# 10LA_org_Raspiado_Updated_Logo_Oct3.net
KiCad netlist of a schematic drawn in EAGLE
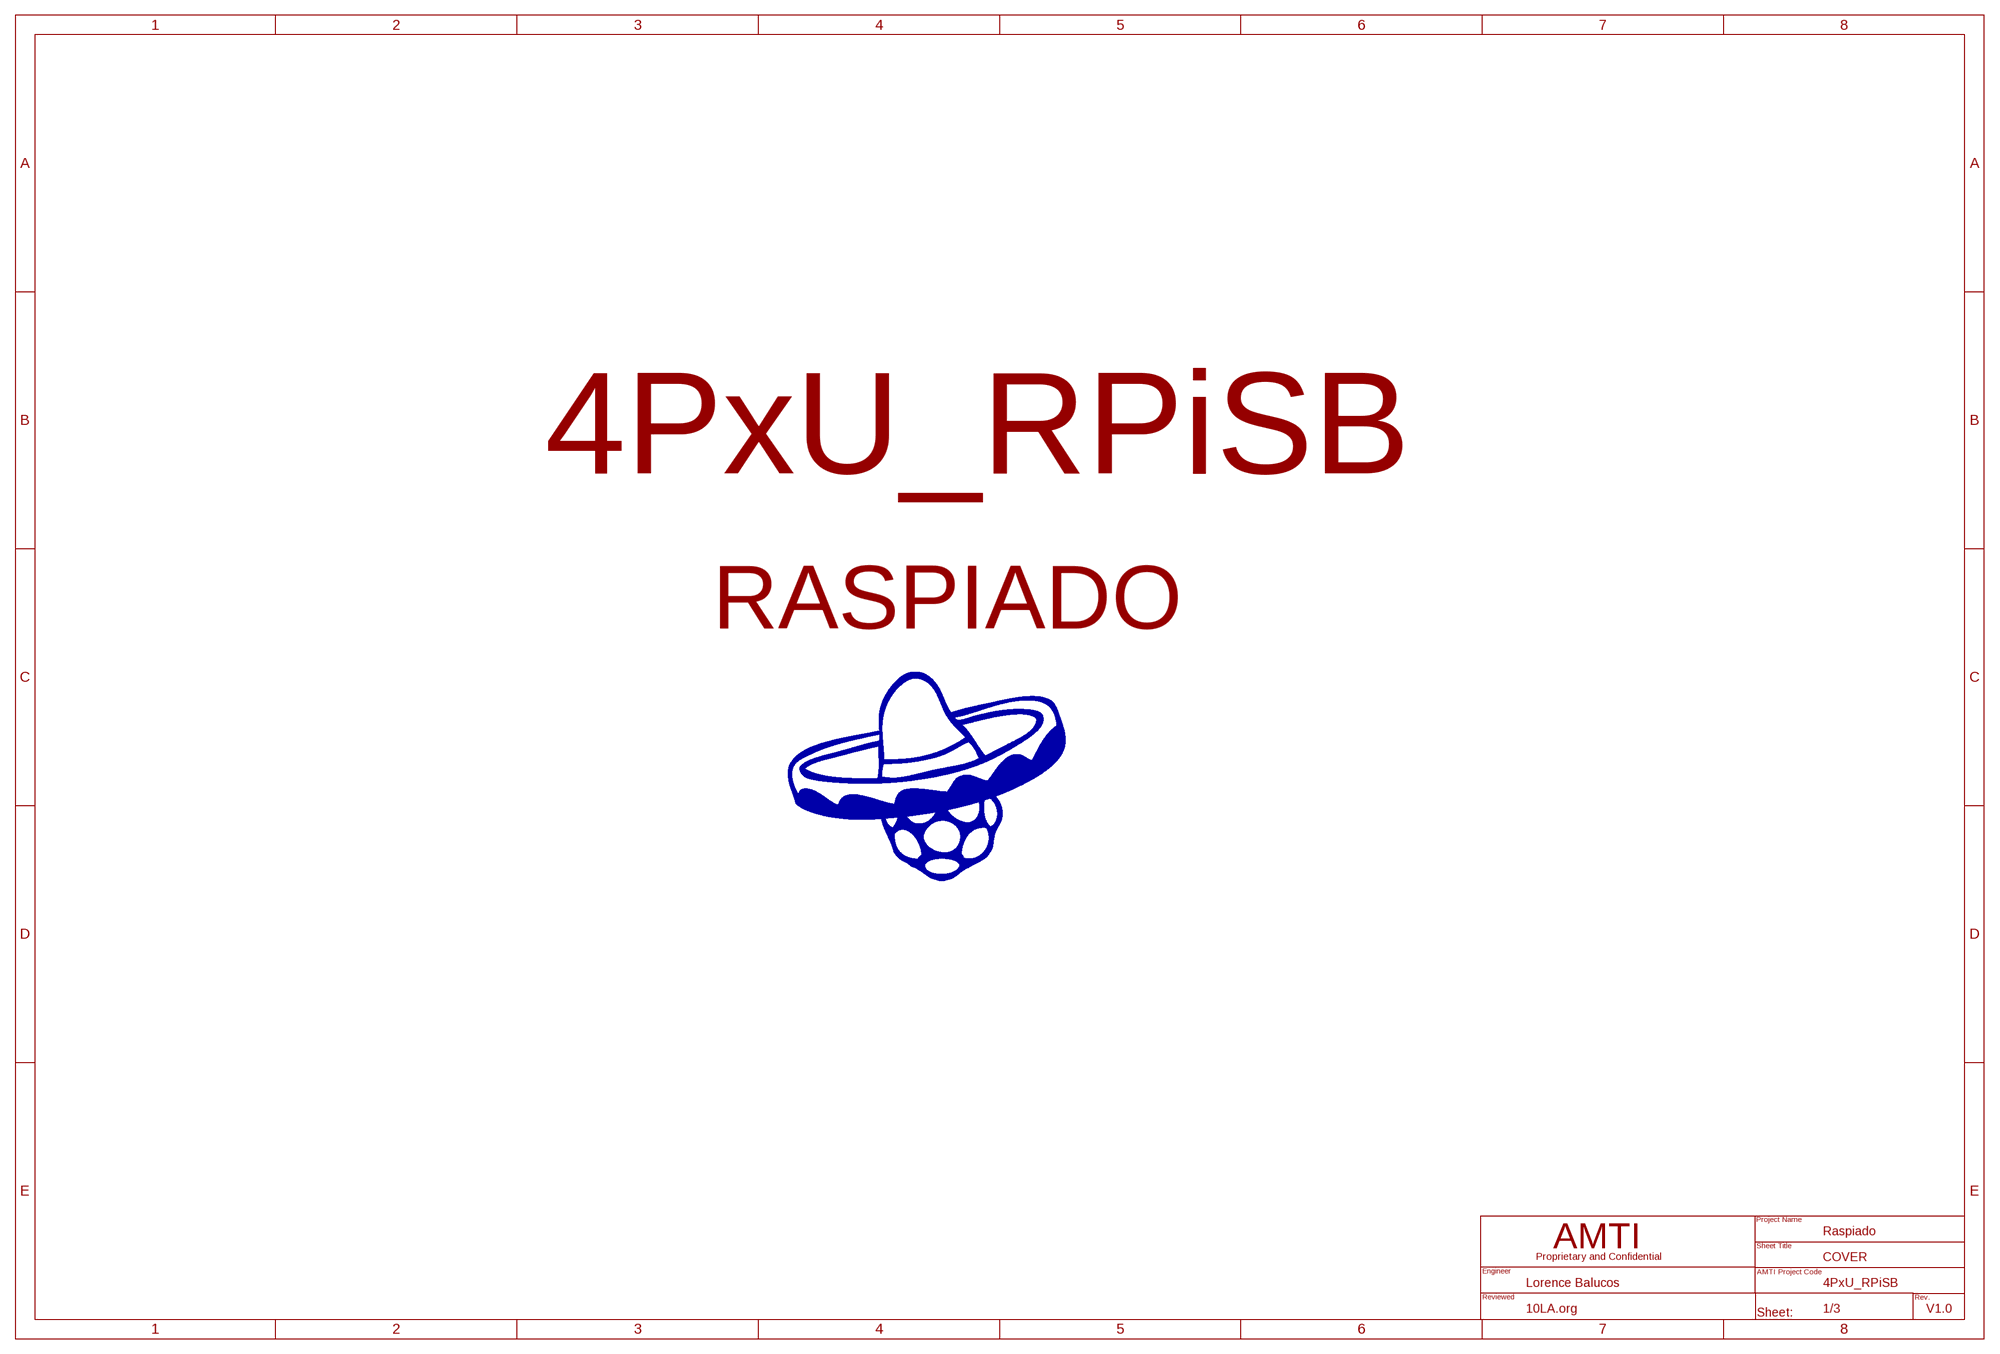
[diagram p0: schematic, sheet 1]
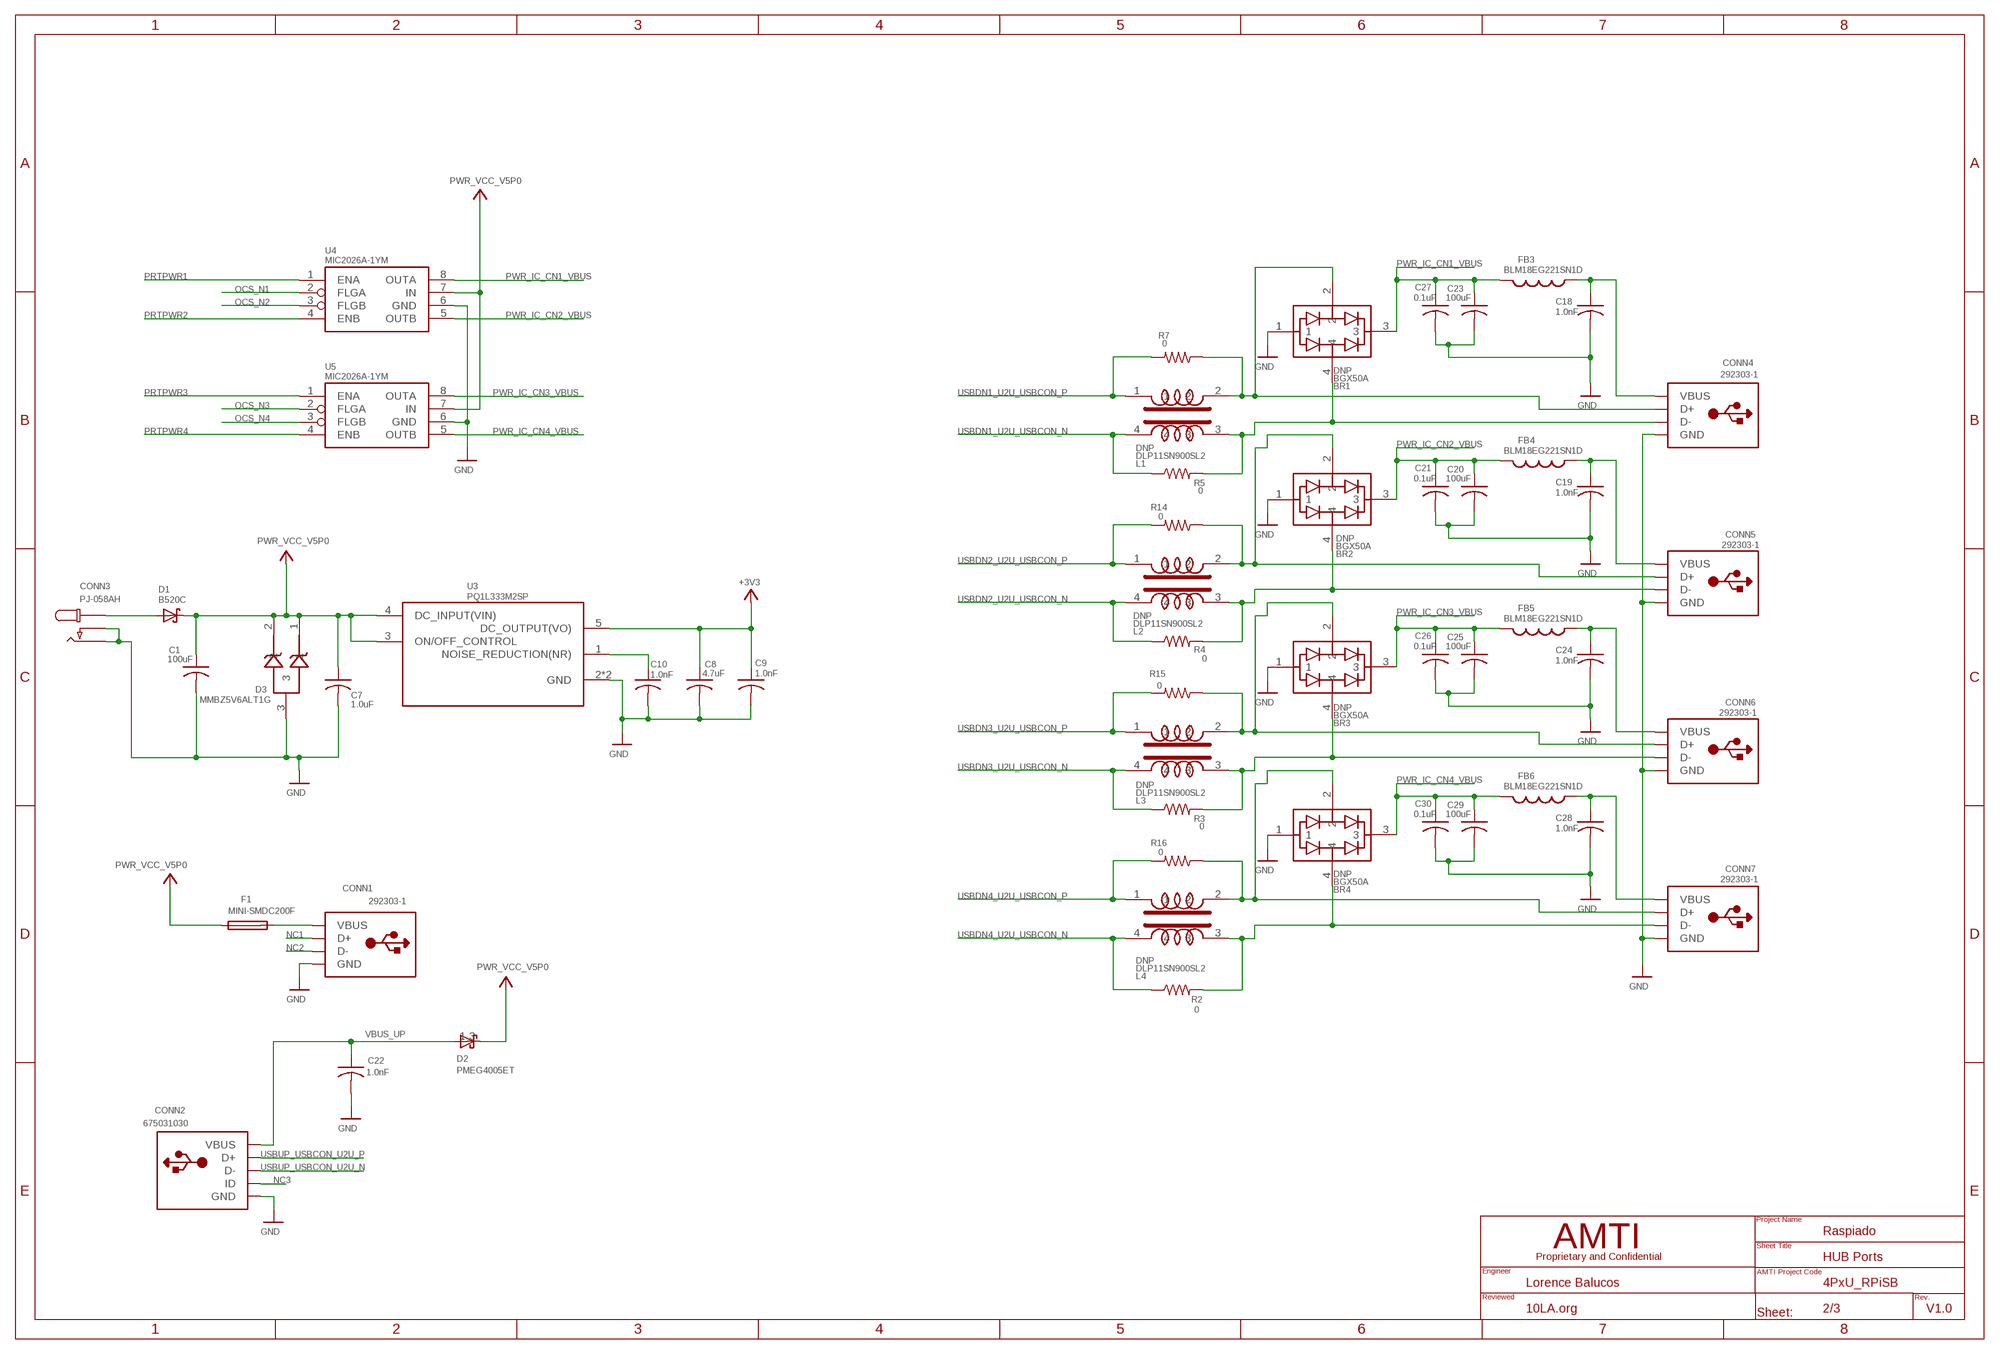
[diagram p1: schematic, sheet 2]
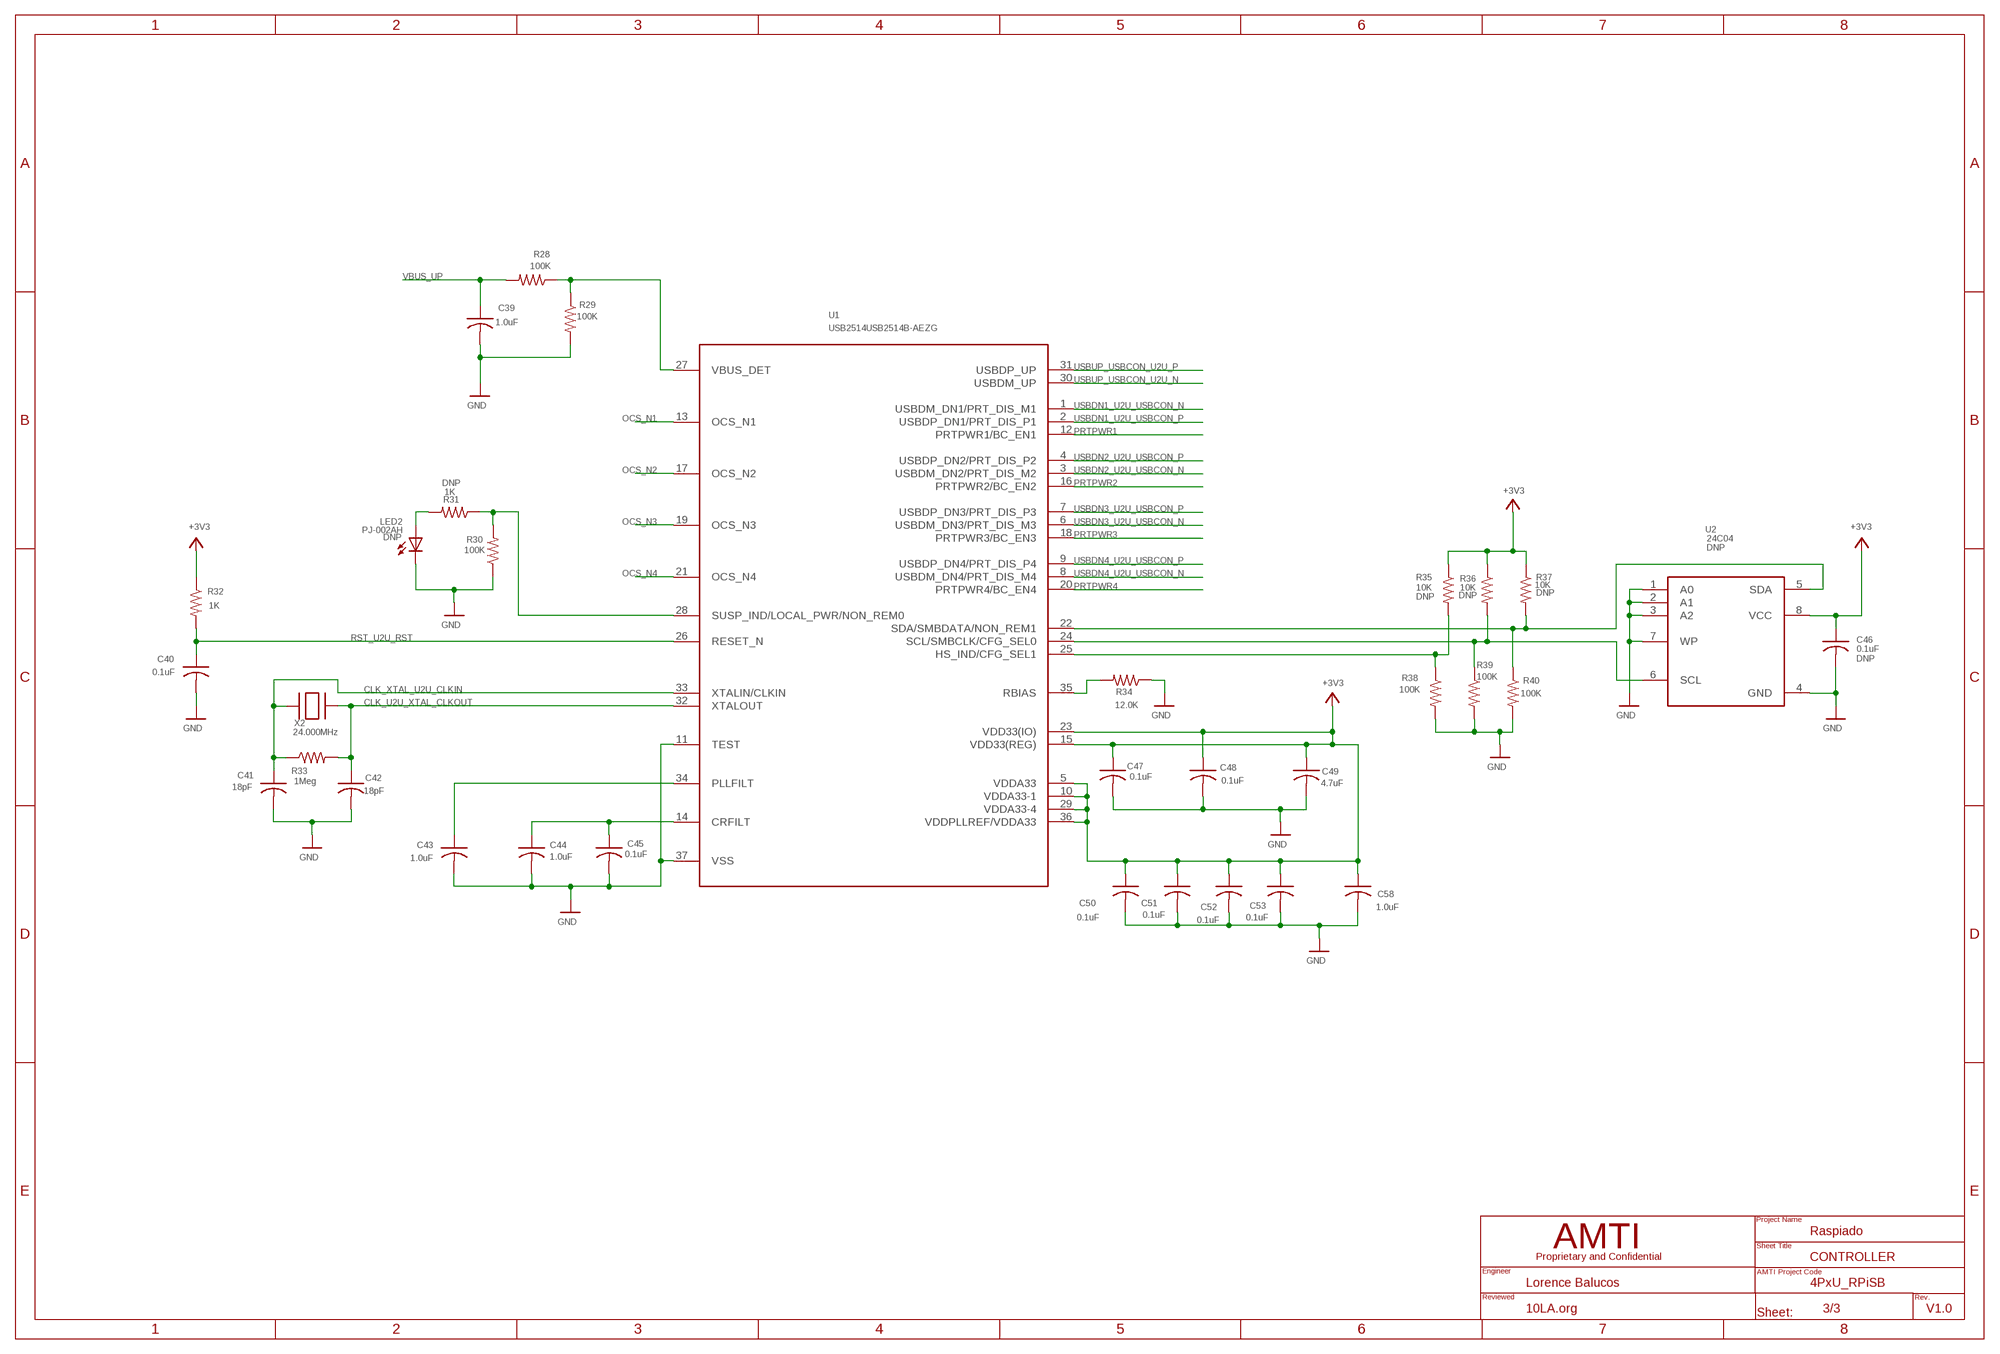
[diagram p2: schematic, sheet 3]

(export (version "E")
  (design (tool "Eeschema 10.0.6"))
  (components
    (comp (ref "BR1")
      (value "BGX50A")
      (footprint "eagle-import:SOT-143")
      (description "Diode, Bridge, Switching, 50v, 140mA, KCAC, SOT-143")
      (fields (field (name "LOAD_OPTION") "DNP"))
      (libsource (lib "eagle-import") (part "BGX50A"))
    )
    (comp (ref "BR2")
      (value "BGX50A")
      (footprint "eagle-import:SOT-143")
      (description "Diode, Bridge, Switching, 50v, 140mA, KCAC, SOT-143")
      (fields (field (name "LOAD_OPTION") "DNP"))
      (libsource (lib "eagle-import") (part "BGX50A"))
    )
    (comp (ref "BR3")
      (value "BGX50A")
      (footprint "eagle-import:SOT-143")
      (description "Diode, Bridge, Switching, 50v, 140mA, KCAC, SOT-143")
      (fields (field (name "LOAD_OPTION") "DNP"))
      (libsource (lib "eagle-import") (part "BGX50A"))
    )
    (comp (ref "BR4")
      (value "BGX50A")
      (footprint "eagle-import:SOT-143")
      (description "Diode, Bridge, Switching, 50v, 140mA, KCAC, SOT-143")
      (fields (field (name "LOAD_OPTION") "DNP"))
      (libsource (lib "eagle-import") (part "BGX50A"))
    )
    (comp (ref "C1")
      (value "100uF")
      (footprint "eagle-import:RADIAL_SMT")
      (description "Capacitor, Low ESR, 100uF, 6.3VDC, 20%, Aluminum, Radial-SMT, 5mm x 5.8mm")
      (libsource (lib "eagle-import") (part "EMZA6R3ADA101ME61G"))
    )
    (comp (ref "C7")
      (value "1.0uF")
      (footprint "eagle-import:C0603")
      (description "Capacitor, 1.0uF, 10%, 6.3V, X5R, 0603")
      (libsource (lib "eagle-import") (part "C-USC0603"))
    )
    (comp (ref "C8")
      (value "4.7uF")
      (footprint "eagle-import:C0603")
      (description "Capacitor, 4.7uF, 6.3VDC, 20%, X5R, 0603")
      (libsource (lib "eagle-import") (part "C-USC0603"))
    )
    (comp (ref "C9")
      (value "1.0nF")
      (footprint "eagle-import:0402")
      (description "Capacitor, 1.0nF, 50VDC, 5%, Standard, 0402")
      (libsource (lib "eagle-import") (part "C-USC0402"))
    )
    (comp (ref "C10")
      (value "1.0nF")
      (footprint "eagle-import:0402")
      (description "Capacitor, 1.0nF, 50VDC, 5%, Standard, 0402")
      (libsource (lib "eagle-import") (part "C-USC0402"))
    )
    (comp (ref "C18")
      (value "1.0nF")
      (footprint "eagle-import:0402")
      (description "Capacitor, 1.0nF, 50VDC, 5%, Standard, 0402")
      (libsource (lib "eagle-import") (part "C-USC0402"))
    )
    (comp (ref "C19")
      (value "1.0nF")
      (footprint "eagle-import:0402")
      (description "Capacitor, 1.0nF, 50VDC, 5%, Standard, 0402")
      (libsource (lib "eagle-import") (part "C-USC0402"))
    )
    (comp (ref "C20")
      (value "100uF")
      (footprint "eagle-import:RADIAL_SMT")
      (description "Capacitor, Low ESR, 100uF, 6.3VDC, 20%, Aluminum, Radial-SMT, 5mm x 5.8mm")
      (libsource (lib "eagle-import") (part "EMZA6R3ADA101ME61G"))
    )
    (comp (ref "C21")
      (value "0.1uF")
      (footprint "eagle-import:0402")
      (description "Capacitor, 0.1uF, 6.3V, 10%, X5R, 0402")
      (libsource (lib "eagle-import") (part "C-USC0402"))
    )
    (comp (ref "C22")
      (value "1.0nF")
      (footprint "eagle-import:0402")
      (description "Capacitor, 1.0nF, 50VDC, 5%, Standard, 0402")
      (libsource (lib "eagle-import") (part "C-USC0402"))
    )
    (comp (ref "C23")
      (value "100uF")
      (footprint "eagle-import:RADIAL_SMT")
      (description "Capacitor, Low ESR, 100uF, 6.3VDC, 20%, Aluminum, Radial-SMT, 5mm x 5.8mm")
      (libsource (lib "eagle-import") (part "EMZA6R3ADA101ME61G"))
    )
    (comp (ref "C24")
      (value "1.0nF")
      (footprint "eagle-import:0402")
      (description "Capacitor, 1.0nF, 50VDC, 5%, Standard, 0402")
      (libsource (lib "eagle-import") (part "C-USC0402"))
    )
    (comp (ref "C25")
      (value "100uF")
      (footprint "eagle-import:RADIAL_SMT")
      (description "Capacitor, Low ESR, 100uF, 6.3VDC, 20%, Aluminum, Radial-SMT, 5mm x 5.8mm")
      (libsource (lib "eagle-import") (part "EMZA6R3ADA101ME61G"))
    )
    (comp (ref "C26")
      (value "0.1uF")
      (footprint "eagle-import:0402")
      (description "Capacitor, 0.1uF, 6.3V, 10%, X5R, 0402")
      (libsource (lib "eagle-import") (part "C-USC0402"))
    )
    (comp (ref "C27")
      (value "0.1uF")
      (footprint "eagle-import:0402")
      (description "Capacitor, 0.1uF, 6.3V, 10%, X5R, 0402")
      (libsource (lib "eagle-import") (part "C-USC0402"))
    )
    (comp (ref "C28")
      (value "1.0nF")
      (footprint "eagle-import:0402")
      (description "Capacitor, 1.0nF, 50VDC, 5%, Standard, 0402")
      (libsource (lib "eagle-import") (part "C-USC0402"))
    )
    (comp (ref "C29")
      (value "100uF")
      (footprint "eagle-import:RADIAL_SMT")
      (description "Capacitor, Low ESR, 100uF, 6.3VDC, 20%, Aluminum, Radial-SMT, 5mm x 5.8mm")
      (libsource (lib "eagle-import") (part "EMZA6R3ADA101ME61G"))
    )
    (comp (ref "C30")
      (value "0.1uF")
      (footprint "eagle-import:0402")
      (description "Capacitor, 0.1uF, 6.3V, 10%, X5R, 0402")
      (libsource (lib "eagle-import") (part "C-USC0402"))
    )
    (comp (ref "CONN1")
      (value "292303-1")
      (footprint "eagle-import:STYLEA,RIGHTANGLE,THROUGH-HOLE")
      (description "Connector, USB, Style A, Right Angle, Through-hole")
      (libsource (lib "eagle-import") (part "USB_292303-1"))
    )
    (comp (ref "CONN2")
      (value "675031030")
      (footprint "eagle-import:MINI_B")
      (description "Connector, 675031030-USB_MINI-B")
      (libsource (lib "eagle-import") (part "675031030-USB_MINI-B"))
    )
    (comp (ref "CONN3")
      (value "PJ-058AH")
      (footprint "eagle-import:PJ-058AH")
      (libsource (lib "eagle-import") (part "PJ-058AH"))
    )
    (comp (ref "CONN4")
      (value "292303-1")
      (footprint "eagle-import:STYLEA,RIGHTANGLE,THROUGH-HOLE")
      (description "Connector, USB, Style A, Right Angle, Through-hole")
      (libsource (lib "eagle-import") (part "USB_292303-1"))
    )
    (comp (ref "CONN5")
      (value "292303-1")
      (footprint "eagle-import:STYLEA,RIGHTANGLE,THROUGH-HOLE")
      (description "Connector, USB, Style A, Right Angle, Through-hole")
      (libsource (lib "eagle-import") (part "USB_292303-1"))
    )
    (comp (ref "CONN6")
      (value "292303-1")
      (footprint "eagle-import:STYLEA,RIGHTANGLE,THROUGH-HOLE")
      (description "Connector, USB, Style A, Right Angle, Through-hole")
      (libsource (lib "eagle-import") (part "USB_292303-1"))
    )
    (comp (ref "CONN7")
      (value "292303-1")
      (footprint "eagle-import:STYLEA,RIGHTANGLE,THROUGH-HOLE")
      (description "Connector, USB, Style A, Right Angle, Through-hole")
      (libsource (lib "eagle-import") (part "USB_292303-1"))
    )
    (comp (ref "D1")
      (value "B520C")
      (footprint "eagle-import:B520C")
      (description "Diode, 5.0A SURFACE MOUNT SCHOTTKY BARRIER RECTIFIER")
      (libsource (lib "eagle-import") (part "B520C"))
    )
    (comp (ref "D2")
      (value "PMEG4005ET")
      (footprint "eagle-import:SOT23")
      (description "Diode ,0.5 A,MEGA Schottky barrier rectifiers,SOT23")
      (libsource (lib "eagle-import") (part "PMEG4005ET"))
    )
    (comp (ref "D3")
      (value "MMBZ5V6ALT1G")
      (footprint "eagle-import:SOT23")
      (description "Diode, TVS, Arrays 5.6V 225mW Dual Common Anode")
      (libsource (lib "eagle-import") (part "MMBZ_ALT1G"))
    )
    (comp (ref "F1")
      (value "MINI-SMDC200F")
      (footprint "eagle-import:MINI-SMDC200F")
      (description "Fuse, PPTC 2A 8V 100A")
      (libsource (lib "eagle-import") (part "MINI-SMDC-200F"))
    )
    (comp (ref "FB3")
      (value "BLM18EG221SN1D")
      (footprint "eagle-import:C0603")
      (description "Ferrite Bead, 220 Ohm, 2A, 0.05DCR, 0603")
      (libsource (lib "eagle-import") (part "BLM18EG221SN1D"))
    )
    (comp (ref "FB4")
      (value "BLM18EG221SN1D")
      (footprint "eagle-import:C0603")
      (description "Ferrite Bead, 220 Ohm, 2A, 0.05DCR, 0603")
      (libsource (lib "eagle-import") (part "BLM18EG221SN1D"))
    )
    (comp (ref "FB5")
      (value "BLM18EG221SN1D")
      (footprint "eagle-import:C0603")
      (description "Ferrite Bead, 220 Ohm, 2A, 0.05DCR, 0603")
      (libsource (lib "eagle-import") (part "BLM18EG221SN1D"))
    )
    (comp (ref "FB6")
      (value "BLM18EG221SN1D")
      (footprint "eagle-import:C0603")
      (description "Ferrite Bead, 220 Ohm, 2A, 0.05DCR, 0603")
      (libsource (lib "eagle-import") (part "BLM18EG221SN1D"))
    )
    (comp (ref "L1")
      (value "DLP11SN900SL2")
      (footprint "eagle-import:0504")
      (description "Inductor, Common Mode Choke, DLP11SN900SL2, 0504")
      (fields (field (name "LOAD_OPTION") "DNP"))
      (libsource (lib "eagle-import") (part "DLP11SN900SL2"))
    )
    (comp (ref "L2")
      (value "DLP11SN900SL2")
      (footprint "eagle-import:0504")
      (description "Inductor, Common Mode Choke, DLP11SN900SL2, 0504")
      (fields (field (name "LOAD_OPTION") "DNP"))
      (libsource (lib "eagle-import") (part "DLP11SN900SL2"))
    )
    (comp (ref "L3")
      (value "DLP11SN900SL2")
      (footprint "eagle-import:0504")
      (description "Inductor, Common Mode Choke, DLP11SN900SL2, 0504")
      (fields (field (name "LOAD_OPTION") "DNP"))
      (libsource (lib "eagle-import") (part "DLP11SN900SL2"))
    )
    (comp (ref "L4")
      (value "DLP11SN900SL2")
      (footprint "eagle-import:0504")
      (description "Inductor, Common Mode Choke, DLP11SN900SL2, 0504")
      (fields (field (name "LOAD_OPTION") "DNP"))
      (libsource (lib "eagle-import") (part "DLP11SN900SL2"))
    )
    (comp (ref "R2")
      (value "0")
      (footprint "eagle-import:R0402")
      (description "Resistor, 0ohm,0402")
      (libsource (lib "eagle-import") (part "R-US_R0402"))
    )
    (comp (ref "R3")
      (value "0")
      (footprint "eagle-import:R0402")
      (description "Resistor, 0ohm,0402")
      (libsource (lib "eagle-import") (part "R-US_R0402"))
    )
    (comp (ref "R4")
      (value "0")
      (footprint "eagle-import:R0402")
      (description "Resistor, 0ohm,0402")
      (libsource (lib "eagle-import") (part "R-US_R0402"))
    )
    (comp (ref "R5")
      (value "0")
      (footprint "eagle-import:R0402")
      (description "Resistor, 0ohm,0402")
      (libsource (lib "eagle-import") (part "R-US_R0402"))
    )
    (comp (ref "R7")
      (value "0")
      (footprint "eagle-import:R0402")
      (description "Resistor, 0ohm,0402")
      (libsource (lib "eagle-import") (part "R-US_R0402"))
    )
    (comp (ref "R14")
      (value "0")
      (footprint "eagle-import:R0402")
      (description "Resistor, 0ohm,0402")
      (libsource (lib "eagle-import") (part "R-US_R0402"))
    )
    (comp (ref "R15")
      (value "0")
      (footprint "eagle-import:R0402")
      (description "Resistor, 0ohm,0402")
      (libsource (lib "eagle-import") (part "R-US_R0402"))
    )
    (comp (ref "R16")
      (value "0")
      (footprint "eagle-import:R0402")
      (description "Resistor, 0ohm,0402")
      (libsource (lib "eagle-import") (part "R-US_R0402"))
    )
    (comp (ref "U3")
      (value "PQ1L333M2SP")
      (footprint "eagle-import:PQ1L333M2SP")
      (description "IC, PQ1L333M2SP, Voltage Regulator, 3.3V, 300mA, Low Dropout, 900mW, SOT-89-5")
      (libsource (lib "eagle-import") (part "PQ1L333M2SP"))
    )
    (comp (ref "U4")
      (value "MIC2026A-1YM")
      (footprint "eagle-import:SO_08")
      (description "IC, MIC2026A-1YM, Power Distribution Switch, SO-8")
      (libsource (lib "eagle-import") (part "MIC2026-1YMA"))
    )
    (comp (ref "U5")
      (value "MIC2026A-1YM")
      (footprint "eagle-import:SO_08")
      (description "IC, MIC2026A-1YM, Power Distribution Switch, SO-8")
      (libsource (lib "eagle-import") (part "MIC2026-1YMA"))
    )
    (comp (ref "C39")
      (value "1.0uF")
      (footprint "eagle-import:C0603")
      (description "Capacitor, 1.0uF, 10%, 6.3V, X5R, 0603")
      (libsource (lib "eagle-import") (part "C-USC0603"))
    )
    (comp (ref "C40")
      (value "0.1uF")
      (footprint "eagle-import:0402")
      (description "Capacitor, 0.1uF, 6.3V, 10%, X5R, 0402")
      (libsource (lib "eagle-import") (part "C-USC0402"))
    )
    (comp (ref "C41")
      (value "18pF")
      (footprint "eagle-import:0402")
      (description "Capacitor, 18pF, 50V, 5%, NPO, 0402")
      (libsource (lib "eagle-import") (part "C-USC0402"))
    )
    (comp (ref "C42")
      (value "18pF")
      (footprint "eagle-import:0402")
      (description "Capacitor, 18pF, 50V, 5%, NPO, 0402")
      (libsource (lib "eagle-import") (part "C-USC0402"))
    )
    (comp (ref "C43")
      (value "1.0uF")
      (footprint "eagle-import:0402")
      (description "Capacitor, 1.0uF, 10%, 6.3V, X5R, 0603")
      (libsource (lib "eagle-import") (part "C-USC0402"))
    )
    (comp (ref "C44")
      (value "1.0uF")
      (footprint "eagle-import:0402")
      (description "Capacitor, 1.0uF, 10%, 6.3V, X5R, 0603")
      (libsource (lib "eagle-import") (part "C-USC0402"))
    )
    (comp (ref "C45")
      (value "0.1uF")
      (footprint "eagle-import:0402")
      (description "Capacitor, 0.1uF, 6.3V, 10%, X5R, 0402")
      (libsource (lib "eagle-import") (part "C-USC0402"))
    )
    (comp (ref "C46")
      (value "0.1uF")
      (footprint "eagle-import:0402")
      (description "Capacitor, 0.1uF, 6.3V, 10%, X5R, 0402")
      (fields (field (name "LOAD_OPTION") "DNP"))
      (libsource (lib "eagle-import") (part "C-USC0402"))
    )
    (comp (ref "C47")
      (value "0.1uF")
      (footprint "eagle-import:0402")
      (description "Capacitor, 0.1uF, 6.3V, 10%, X5R, 0402")
      (libsource (lib "eagle-import") (part "C-USC0402"))
    )
    (comp (ref "C48")
      (value "0.1uF")
      (footprint "eagle-import:0402")
      (description "Capacitor, 0.1uF, 6.3V, 10%, X5R, 0402")
      (libsource (lib "eagle-import") (part "C-USC0402"))
    )
    (comp (ref "C49")
      (value "4.7uF")
      (footprint "eagle-import:C0603")
      (description "Capacitor, 4.7uF, 6.3VDC, 20%, X5R, 0603")
      (libsource (lib "eagle-import") (part "C-USC0603"))
    )
    (comp (ref "C50")
      (value "0.1uF")
      (footprint "eagle-import:0402")
      (description "Capacitor, 0.1uF, 6.3V, 10%, X5R, 0402")
      (libsource (lib "eagle-import") (part "C-USC0402"))
    )
    (comp (ref "C51")
      (value "0.1uF")
      (footprint "eagle-import:0402")
      (description "Capacitor, 0.1uF, 6.3V, 10%, X5R, 0402")
      (libsource (lib "eagle-import") (part "C-USC0402"))
    )
    (comp (ref "C52")
      (value "0.1uF")
      (footprint "eagle-import:0402")
      (description "Capacitor, 0.1uF, 6.3V, 10%, X5R, 0402")
      (libsource (lib "eagle-import") (part "C-USC0402"))
    )
    (comp (ref "C53")
      (value "0.1uF")
      (footprint "eagle-import:0402")
      (description "Capacitor, 0.1uF, 6.3V, 10%, X5R, 0402")
      (libsource (lib "eagle-import") (part "C-USC0402"))
    )
    (comp (ref "C58")
      (value "1.0uF")
      (footprint "eagle-import:C0603")
      (description "Capacitor, 1.0uF, 10%, 6.3V, X5R, 0603")
      (libsource (lib "eagle-import") (part "C-USC0603"))
    )
    (comp (ref "LED2")
      (value "PJ-002AH")
      (footprint "eagle-import:0603")
      (description "LED, CHIPLED 0603")
      (fields (field (name "LOAD_OPTION") "DNP"))
      (libsource (lib "eagle-import") (part "LEDCHIPLED_0603"))
    )
    (comp (ref "R28")
      (value "100K")
      (footprint "eagle-import:R0603")
      (description "Resistor, 100K, 5%, 1/16W, 0603")
      (libsource (lib "eagle-import") (part "R-US_R0603"))
    )
    (comp (ref "R29")
      (value "100K")
      (footprint "eagle-import:R0603")
      (description "Resistor, 100K, 5%, 1/16W, 0603")
      (libsource (lib "eagle-import") (part "R-US_R0603"))
    )
    (comp (ref "R30")
      (value "100K")
      (footprint "eagle-import:R0603")
      (description "Resistor, 100K, 5%, 1/16W, 0603")
      (libsource (lib "eagle-import") (part "R-US_R0603"))
    )
    (comp (ref "R31")
      (value "1K")
      (footprint "eagle-import:R0603")
      (description "Resistor, 1K, 5%, 1/16W, 0603")
      (fields (field (name "LOAD_OPTION") "DNP"))
      (libsource (lib "eagle-import") (part "R-US_R0603"))
    )
    (comp (ref "R32")
      (value "1K")
      (footprint "eagle-import:R0603")
      (description "Resistor, 1K, 5%, 1/16W, 0603")
      (libsource (lib "eagle-import") (part "R-US_R0603"))
    )
    (comp (ref "R33")
      (value "1Meg")
      (footprint "eagle-import:R0603")
      (description "Resistor, 1Meg, 5%, 1/16W, 0603")
      (libsource (lib "eagle-import") (part "R-US_R0603"))
    )
    (comp (ref "R34")
      (value "12.0K")
      (footprint "eagle-import:R0603")
      (description "Resistor, 12.0K, 1%, 1/16W, 0603")
      (libsource (lib "eagle-import") (part "R-US_R0603"))
    )
    (comp (ref "R35")
      (value "10K")
      (footprint "eagle-import:R0603")
      (description "Resistor, 10.0K, 1%, 1/16W, 0603")
      (fields (field (name "LOAD_OPTION") "DNP"))
      (libsource (lib "eagle-import") (part "R-US_R0603"))
    )
    (comp (ref "R36")
      (value "10K")
      (footprint "eagle-import:R0603")
      (description "Resistor, 10.0K, 1%, 1/16W, 0603")
      (fields (field (name "LOAD_OPTION") "DNP"))
      (libsource (lib "eagle-import") (part "R-US_R0603"))
    )
    (comp (ref "R37")
      (value "10K")
      (footprint "eagle-import:R0603")
      (description "Resistor, 10.0K, 1%, 1/16W, 0603")
      (fields (field (name "LOAD_OPTION") "DNP"))
      (libsource (lib "eagle-import") (part "R-US_R0603"))
    )
    (comp (ref "R38")
      (value "100K")
      (footprint "eagle-import:R0603")
      (description "Resistor, 100K, 5%, 1/16W, 0603")
      (libsource (lib "eagle-import") (part "R-US_R0603"))
    )
    (comp (ref "R39")
      (value "100K")
      (footprint "eagle-import:R0603")
      (description "Resistor, 100K, 5%, 1/16W, 0603")
      (libsource (lib "eagle-import") (part "R-US_R0603"))
    )
    (comp (ref "R40")
      (value "100K")
      (footprint "eagle-import:R0603")
      (description "Resistor, 100K, 5%, 1/16W, 0603")
      (libsource (lib "eagle-import") (part "R-US_R0603"))
    )
    (comp (ref "U1")
      (value "USB2514USB2514B-AEZG")
      (footprint "eagle-import:QFN36")
      (description "IC, USB2514B, 4 Port USB 2.0 Hub, QFN36")
      (libsource (lib "eagle-import") (part "USB2514USB2514B-AEZG"))
    )
    (comp (ref "U2")
      (value "24C04")
      (footprint "eagle-import:SO-8")
      (description "IC, EEPROM,3V to 5.5V for ST24x04,")
      (fields (field (name "LOAD_OPTION") "DNP"))
      (libsource (lib "eagle-import") (part "24C04"))
    )
    (comp (ref "X2")
      (value "24.000MHz")
      (footprint "eagle-import:HC-49SMT")
      (description "Crystal, 24.000MHz, 50ppm, 18pF, HC-49SMT")
      (libsource (lib "eagle-import") (part "HCM49-24.000MABJ-UT"))
    )
  )
  (nets
    (net (code "1") (name "+3V3") (class "Default")
      (node (ref "C46") (pin "1") (pinfunction "1_1") (pintype "passive"))
      (node (ref "C47") (pin "1") (pinfunction "1_1") (pintype "passive"))
      (node (ref "C48") (pin "1") (pinfunction "1_1") (pintype "passive"))
      (node (ref "C49") (pin "1") (pinfunction "1_1") (pintype "passive"))
      (node (ref "C50") (pin "1") (pinfunction "1_1") (pintype "passive"))
      (node (ref "C51") (pin "1") (pinfunction "1_1") (pintype "passive"))
      (node (ref "C52") (pin "1") (pinfunction "1_1") (pintype "passive"))
      (node (ref "C53") (pin "1") (pinfunction "1_1") (pintype "passive"))
      (node (ref "C58") (pin "1") (pinfunction "1_1") (pintype "passive"))
      (node (ref "C8") (pin "1") (pinfunction "1_1") (pintype "passive"))
      (node (ref "C9") (pin "1") (pinfunction "1_1") (pintype "passive"))
      (node (ref "R32") (pin "1") (pinfunction "1_1") (pintype "passive"))
      (node (ref "R35") (pin "1") (pinfunction "1_1") (pintype "passive"))
      (node (ref "R36") (pin "1") (pinfunction "1_1") (pintype "passive"))
      (node (ref "R37") (pin "1") (pinfunction "1_1") (pintype "passive"))
      (node (ref "U1") (pin "10") (pinfunction "VDDA33-1_10") (pintype "bidirectional"))
      (node (ref "U1") (pin "15") (pinfunction "VDD33(REG)_15") (pintype "bidirectional"))
      (node (ref "U1") (pin "23") (pinfunction "VDD33(IO)_23") (pintype "bidirectional"))
      (node (ref "U1") (pin "29") (pinfunction "VDDA33-4_29") (pintype "bidirectional"))
      (node (ref "U1") (pin "36") (pinfunction "VDDPLLREF/VDDA33_36") (pintype "bidirectional"))
      (node (ref "U1") (pin "5") (pinfunction "VDDA33_5") (pintype "bidirectional"))
      (node (ref "U2") (pin "8") (pinfunction "VCC_8") (pintype "bidirectional"))
      (node (ref "U3") (pin "5") (pinfunction "DC_OUTPUT(VO)_5") (pintype "bidirectional"))
    )
    (net (code "2") (name "CLK_U2U_XTAL_CLKOUT") (class "Default")
      (node (ref "C42") (pin "1") (pinfunction "1_1") (pintype "passive"))
      (node (ref "R33") (pin "2") (pinfunction "2_2") (pintype "passive"))
      (node (ref "U1") (pin "32") (pinfunction "XTALOUT_32") (pintype "bidirectional"))
      (node (ref "X2") (pin "2") (pinfunction "P$2_2") (pintype "bidirectional"))
    )
    (net (code "3") (name "CLK_XTAL_U2U_CLKIN") (class "Default")
      (node (ref "C41") (pin "1") (pinfunction "1_1") (pintype "passive"))
      (node (ref "R33") (pin "1") (pinfunction "1_1") (pintype "passive"))
      (node (ref "U1") (pin "33") (pinfunction "XTALIN/CLKIN_33") (pintype "bidirectional"))
      (node (ref "X2") (pin "1") (pinfunction "P$1_1") (pintype "bidirectional"))
    )
    (net (code "4") (name "GND") (class "Default")
      (node (ref "BR1") (pin "1") (pinfunction "1_1") (pintype "bidirectional"))
      (node (ref "BR2") (pin "1") (pinfunction "1_1") (pintype "bidirectional"))
      (node (ref "BR3") (pin "1") (pinfunction "1_1") (pintype "bidirectional"))
      (node (ref "BR4") (pin "1") (pinfunction "1_1") (pintype "bidirectional"))
      (node (ref "C1") (pin "-") (pinfunction "2_-") (pintype "passive"))
      (node (ref "C10") (pin "2") (pinfunction "2_2") (pintype "passive"))
      (node (ref "C18") (pin "2") (pinfunction "2_2") (pintype "passive"))
      (node (ref "C19") (pin "2") (pinfunction "2_2") (pintype "passive"))
      (node (ref "C20") (pin "-") (pinfunction "2_-") (pintype "passive"))
      (node (ref "C21") (pin "2") (pinfunction "2_2") (pintype "passive"))
      (node (ref "C22") (pin "2") (pinfunction "2_2") (pintype "passive"))
      (node (ref "C23") (pin "-") (pinfunction "2_-") (pintype "passive"))
      (node (ref "C24") (pin "2") (pinfunction "2_2") (pintype "passive"))
      (node (ref "C25") (pin "-") (pinfunction "2_-") (pintype "passive"))
      (node (ref "C26") (pin "2") (pinfunction "2_2") (pintype "passive"))
      (node (ref "C27") (pin "2") (pinfunction "2_2") (pintype "passive"))
      (node (ref "C28") (pin "2") (pinfunction "2_2") (pintype "passive"))
      (node (ref "C29") (pin "-") (pinfunction "2_-") (pintype "passive"))
      (node (ref "C30") (pin "2") (pinfunction "2_2") (pintype "passive"))
      (node (ref "C39") (pin "2") (pinfunction "2_2") (pintype "passive"))
      (node (ref "C40") (pin "2") (pinfunction "2_2") (pintype "passive"))
      (node (ref "C41") (pin "2") (pinfunction "2_2") (pintype "passive"))
      (node (ref "C42") (pin "2") (pinfunction "2_2") (pintype "passive"))
      (node (ref "C43") (pin "2") (pinfunction "2_2") (pintype "passive"))
      (node (ref "C44") (pin "2") (pinfunction "2_2") (pintype "passive"))
      (node (ref "C45") (pin "2") (pinfunction "2_2") (pintype "passive"))
      (node (ref "C46") (pin "2") (pinfunction "2_2") (pintype "passive"))
      (node (ref "C47") (pin "2") (pinfunction "2_2") (pintype "passive"))
      (node (ref "C48") (pin "2") (pinfunction "2_2") (pintype "passive"))
      (node (ref "C49") (pin "2") (pinfunction "2_2") (pintype "passive"))
      (node (ref "C50") (pin "2") (pinfunction "2_2") (pintype "passive"))
      (node (ref "C51") (pin "2") (pinfunction "2_2") (pintype "passive"))
      (node (ref "C52") (pin "2") (pinfunction "2_2") (pintype "passive"))
      (node (ref "C53") (pin "2") (pinfunction "2_2") (pintype "passive"))
      (node (ref "C58") (pin "2") (pinfunction "2_2") (pintype "passive"))
      (node (ref "C7") (pin "2") (pinfunction "2_2") (pintype "passive"))
      (node (ref "C8") (pin "2") (pinfunction "2_2") (pintype "passive"))
      (node (ref "C9") (pin "2") (pinfunction "2_2") (pintype "passive"))
      (node (ref "CONN1") (pin "GND") (pinfunction "GND_GND") (pintype "power_in"))
      (node (ref "CONN1") (pin "GND1") (pinfunction "GND_GND1") (pintype "power_in"))
      (node (ref "CONN1") (pin "GND2") (pinfunction "GND_GND2") (pintype "power_in"))
      (node (ref "CONN2") (pin "GND") (pinfunction "GND_GND") (pintype "power_in"))
      (node (ref "CONN2") (pin "GND1") (pinfunction "GND_GND1") (pintype "power_in"))
      (node (ref "CONN2") (pin "GND2") (pinfunction "GND_GND2") (pintype "power_in"))
      (node (ref "CONN2") (pin "GND3") (pinfunction "GND_GND3") (pintype "power_in"))
      (node (ref "CONN2") (pin "GND4") (pinfunction "GND_GND4") (pintype "power_in"))
      (node (ref "CONN3") (pin "2") (pinfunction "2_2") (pintype "bidirectional"))
      (node (ref "CONN3") (pin "3") (pinfunction "3_3") (pintype "bidirectional"))
      (node (ref "CONN4") (pin "GND") (pinfunction "GND_GND") (pintype "power_in"))
      (node (ref "CONN4") (pin "GND1") (pinfunction "GND_GND1") (pintype "power_in"))
      (node (ref "CONN4") (pin "GND2") (pinfunction "GND_GND2") (pintype "power_in"))
      (node (ref "CONN5") (pin "GND") (pinfunction "GND_GND") (pintype "power_in"))
      (node (ref "CONN5") (pin "GND1") (pinfunction "GND_GND1") (pintype "power_in"))
      (node (ref "CONN5") (pin "GND2") (pinfunction "GND_GND2") (pintype "power_in"))
      (node (ref "CONN6") (pin "GND") (pinfunction "GND_GND") (pintype "power_in"))
      (node (ref "CONN6") (pin "GND1") (pinfunction "GND_GND1") (pintype "power_in"))
      (node (ref "CONN6") (pin "GND2") (pinfunction "GND_GND2") (pintype "power_in"))
      (node (ref "CONN7") (pin "GND") (pinfunction "GND_GND") (pintype "power_in"))
      (node (ref "CONN7") (pin "GND1") (pinfunction "GND_GND1") (pintype "power_in"))
      (node (ref "CONN7") (pin "GND2") (pinfunction "GND_GND2") (pintype "power_in"))
      (node (ref "D3") (pin "3") (pinfunction "3_3") (pintype "bidirectional"))
      (node (ref "LED2") (pin "C") (pinfunction "C_C") (pintype "passive"))
      (node (ref "R29") (pin "2") (pinfunction "2_2") (pintype "passive"))
      (node (ref "R30") (pin "1") (pinfunction "1_1") (pintype "passive"))
      (node (ref "R34") (pin "1") (pinfunction "1_1") (pintype "passive"))
      (node (ref "R38") (pin "2") (pinfunction "2_2") (pintype "passive"))
      (node (ref "R39") (pin "2") (pinfunction "2_2") (pintype "passive"))
      (node (ref "R40") (pin "2") (pinfunction "2_2") (pintype "passive"))
      (node (ref "U1") (pin "11") (pinfunction "TEST_11") (pintype "bidirectional"))
      (node (ref "U1") (pin "37") (pinfunction "VSS_37") (pintype "bidirectional"))
      (node (ref "U2") (pin "1") (pinfunction "A0_1") (pintype "bidirectional"))
      (node (ref "U2") (pin "2") (pinfunction "A1_2") (pintype "bidirectional"))
      (node (ref "U2") (pin "3") (pinfunction "A2_3") (pintype "bidirectional"))
      (node (ref "U2") (pin "4") (pinfunction "GND_4") (pintype "bidirectional"))
      (node (ref "U2") (pin "7") (pinfunction "WP_7") (pintype "bidirectional"))
      (node (ref "U3") (pin "2") (pinfunction "GND_2") (pintype "bidirectional"))
      (node (ref "U3") (pin "P$3") (pinfunction "GND_P$3") (pintype "bidirectional"))
      (node (ref "U4") (pin "6") (pinfunction "GND_6") (pintype "power_in"))
      (node (ref "U5") (pin "6") (pinfunction "GND_6") (pintype "power_in"))
    )
    (net (code "5") (name "NC1") (class "Default")
      (node (ref "CONN1") (pin "SIG2") (pinfunction "D+_SIG2") (pintype "bidirectional"))
    )
    (net (code "6") (name "NC2") (class "Default")
      (node (ref "CONN1") (pin "SIG1") (pinfunction "D-_SIG1") (pintype "bidirectional"))
    )
    (net (code "7") (name "NC3") (class "Default")
      (node (ref "CONN2") (pin "ID") (pinfunction "ID_ID") (pintype "bidirectional"))
    )
    (net (code "8") (name "Net-(C18-Pad1)") (class "Default")
      (node (ref "C18") (pin "1") (pinfunction "1_1") (pintype "passive"))
      (node (ref "CONN4") (pin "VBUS") (pinfunction "VBUS_VBUS") (pintype "power_in"))
      (node (ref "FB3") (pin "1") (pinfunction "1_1") (pintype "passive"))
    )
    (net (code "9") (name "Net-(C19-Pad1)") (class "Default")
      (node (ref "C19") (pin "1") (pinfunction "1_1") (pintype "passive"))
      (node (ref "CONN5") (pin "VBUS") (pinfunction "VBUS_VBUS") (pintype "power_in"))
      (node (ref "FB4") (pin "1") (pinfunction "1_1") (pintype "passive"))
    )
    (net (code "10") (name "Net-(C24-Pad1)") (class "Default")
      (node (ref "C24") (pin "1") (pinfunction "1_1") (pintype "passive"))
      (node (ref "CONN6") (pin "VBUS") (pinfunction "VBUS_VBUS") (pintype "power_in"))
      (node (ref "FB5") (pin "1") (pinfunction "1_1") (pintype "passive"))
    )
    (net (code "11") (name "Net-(C28-Pad1)") (class "Default")
      (node (ref "C28") (pin "1") (pinfunction "1_1") (pintype "passive"))
      (node (ref "CONN7") (pin "VBUS") (pinfunction "VBUS_VBUS") (pintype "power_in"))
      (node (ref "FB6") (pin "1") (pinfunction "1_1") (pintype "passive"))
    )
    (net (code "12") (name "Net-(CONN1-PadVBUS)") (class "Default")
      (node (ref "CONN1") (pin "VBUS") (pinfunction "VBUS_VBUS") (pintype "power_in"))
      (node (ref "F1") (pin "2") (pinfunction "2_2") (pintype "passive"))
    )
    (net (code "13") (name "Net-(CONN4-D+)") (class "Default")
      (node (ref "BR1") (pin "2") (pinfunction "2_2") (pintype "bidirectional"))
      (node (ref "CONN4") (pin "SIG2") (pinfunction "D+_SIG2") (pintype "bidirectional"))
      (node (ref "L1") (pin "2") (pinfunction "2_2") (pintype "bidirectional"))
      (node (ref "R7") (pin "1") (pinfunction "1_1") (pintype "passive"))
    )
    (net (code "14") (name "Net-(CONN4-D-)") (class "Default")
      (node (ref "BR1") (pin "4") (pinfunction "4_4") (pintype "bidirectional"))
      (node (ref "CONN4") (pin "SIG1") (pinfunction "D-_SIG1") (pintype "bidirectional"))
      (node (ref "L1") (pin "3") (pinfunction "3_3") (pintype "bidirectional"))
      (node (ref "R5") (pin "2") (pinfunction "2_2") (pintype "passive"))
    )
    (net (code "15") (name "Net-(CONN5-D+)") (class "Default")
      (node (ref "BR2") (pin "2") (pinfunction "2_2") (pintype "bidirectional"))
      (node (ref "CONN5") (pin "SIG2") (pinfunction "D+_SIG2") (pintype "bidirectional"))
      (node (ref "L2") (pin "2") (pinfunction "2_2") (pintype "bidirectional"))
      (node (ref "R14") (pin "1") (pinfunction "1_1") (pintype "passive"))
    )
    (net (code "16") (name "Net-(CONN5-D-)") (class "Default")
      (node (ref "BR2") (pin "4") (pinfunction "4_4") (pintype "bidirectional"))
      (node (ref "CONN5") (pin "SIG1") (pinfunction "D-_SIG1") (pintype "bidirectional"))
      (node (ref "L2") (pin "3") (pinfunction "3_3") (pintype "bidirectional"))
      (node (ref "R4") (pin "2") (pinfunction "2_2") (pintype "passive"))
    )
    (net (code "17") (name "Net-(CONN6-D+)") (class "Default")
      (node (ref "BR3") (pin "2") (pinfunction "2_2") (pintype "bidirectional"))
      (node (ref "CONN6") (pin "SIG2") (pinfunction "D+_SIG2") (pintype "bidirectional"))
      (node (ref "L3") (pin "2") (pinfunction "2_2") (pintype "bidirectional"))
      (node (ref "R15") (pin "1") (pinfunction "1_1") (pintype "passive"))
    )
    (net (code "18") (name "Net-(CONN6-D-)") (class "Default")
      (node (ref "BR3") (pin "4") (pinfunction "4_4") (pintype "bidirectional"))
      (node (ref "CONN6") (pin "SIG1") (pinfunction "D-_SIG1") (pintype "bidirectional"))
      (node (ref "L3") (pin "3") (pinfunction "3_3") (pintype "bidirectional"))
      (node (ref "R3") (pin "2") (pinfunction "2_2") (pintype "passive"))
    )
    (net (code "19") (name "Net-(CONN7-D+)") (class "Default")
      (node (ref "BR4") (pin "2") (pinfunction "2_2") (pintype "bidirectional"))
      (node (ref "CONN7") (pin "SIG2") (pinfunction "D+_SIG2") (pintype "bidirectional"))
      (node (ref "L4") (pin "2") (pinfunction "2_2") (pintype "bidirectional"))
      (node (ref "R16") (pin "1") (pinfunction "1_1") (pintype "passive"))
    )
    (net (code "20") (name "Net-(CONN7-D-)") (class "Default")
      (node (ref "BR4") (pin "4") (pinfunction "4_4") (pintype "bidirectional"))
      (node (ref "CONN7") (pin "SIG1") (pinfunction "D-_SIG1") (pintype "bidirectional"))
      (node (ref "L4") (pin "3") (pinfunction "3_3") (pintype "bidirectional"))
      (node (ref "R2") (pin "2") (pinfunction "2_2") (pintype "passive"))
    )
    (net (code "21") (name "Net-(D1-1)") (class "Default")
      (node (ref "CONN3") (pin "1") (pinfunction "1_1") (pintype "bidirectional"))
      (node (ref "D1") (pin "P$1") (pinfunction "1_P$1") (pintype "passive"))
    )
    (net (code "22") (name "Net-(LED2-PadA)") (class "Default")
      (node (ref "LED2") (pin "A") (pinfunction "A_A") (pintype "passive"))
      (node (ref "R31") (pin "2") (pinfunction "2_2") (pintype "passive"))
    )
    (net (code "23") (name "Net-(U1-CRFILT)") (class "Default")
      (node (ref "C44") (pin "1") (pinfunction "1_1") (pintype "passive"))
      (node (ref "C45") (pin "1") (pinfunction "1_1") (pintype "passive"))
      (node (ref "U1") (pin "14") (pinfunction "CRFILT_14") (pintype "bidirectional"))
    )
    (net (code "24") (name "Net-(U1-HS_IND{slash}CFG_SEL1)") (class "Default")
      (node (ref "R35") (pin "2") (pinfunction "2_2") (pintype "passive"))
      (node (ref "R38") (pin "1") (pinfunction "1_1") (pintype "passive"))
      (node (ref "U1") (pin "25") (pinfunction "HS_IND/CFG_SEL1_25") (pintype "bidirectional"))
    )
    (net (code "25") (name "Net-(U1-PLLFILT)") (class "Default")
      (node (ref "C43") (pin "1") (pinfunction "1_1") (pintype "passive"))
      (node (ref "U1") (pin "34") (pinfunction "PLLFILT_34") (pintype "bidirectional"))
    )
    (net (code "26") (name "Net-(U1-RBIAS)") (class "Default")
      (node (ref "R34") (pin "2") (pinfunction "2_2") (pintype "passive"))
      (node (ref "U1") (pin "35") (pinfunction "RBIAS_35") (pintype "bidirectional"))
    )
    (net (code "27") (name "Net-(U1-SCL{slash}SMBCLK{slash}CFG_SEL0)") (class "Default")
      (node (ref "R36") (pin "2") (pinfunction "2_2") (pintype "passive"))
      (node (ref "R39") (pin "1") (pinfunction "1_1") (pintype "passive"))
      (node (ref "U1") (pin "24") (pinfunction "SCL/SMBCLK/CFG_SEL0_24") (pintype "bidirectional"))
      (node (ref "U2") (pin "6") (pinfunction "SCL_6") (pintype "bidirectional"))
    )
    (net (code "28") (name "Net-(U1-SDA{slash}SMBDATA{slash}NON_REM1)") (class "Default")
      (node (ref "R37") (pin "2") (pinfunction "2_2") (pintype "passive"))
      (node (ref "R40") (pin "1") (pinfunction "1_1") (pintype "passive"))
      (node (ref "U1") (pin "22") (pinfunction "SDA/SMBDATA/NON_REM1_22") (pintype "bidirectional"))
      (node (ref "U2") (pin "5") (pinfunction "SDA_5") (pintype "bidirectional"))
    )
    (net (code "29") (name "Net-(U1-SUSP_IND{slash}LOCAL_PWR{slash}NON_REM0)") (class "Default")
      (node (ref "R30") (pin "2") (pinfunction "2_2") (pintype "passive"))
      (node (ref "R31") (pin "1") (pinfunction "1_1") (pintype "passive"))
      (node (ref "U1") (pin "28") (pinfunction "SUSP_IND/LOCAL_PWR/NON_REM0_28") (pintype "bidirectional"))
    )
    (net (code "30") (name "Net-(U1-VBUS_DET)") (class "Default")
      (node (ref "R28") (pin "1") (pinfunction "1_1") (pintype "passive"))
      (node (ref "R29") (pin "1") (pinfunction "1_1") (pintype "passive"))
      (node (ref "U1") (pin "27") (pinfunction "VBUS_DET_27") (pintype "bidirectional"))
    )
    (net (code "31") (name "Net-(U3-NOISE_REDUCTION(NR))") (class "Default")
      (node (ref "C10") (pin "1") (pinfunction "1_1") (pintype "passive"))
      (node (ref "U3") (pin "1") (pinfunction "NOISE_REDUCTION(NR)_1") (pintype "bidirectional"))
    )
    (net (code "32") (name "OCS_N1") (class "Default")
      (node (ref "U1") (pin "13") (pinfunction "OCS_N1_13") (pintype "bidirectional"))
      (node (ref "U4") (pin "2") (pinfunction "FLGA_2") (pintype "open_collector"))
    )
    (net (code "33") (name "OCS_N2") (class "Default")
      (node (ref "U1") (pin "17") (pinfunction "OCS_N2_17") (pintype "bidirectional"))
      (node (ref "U4") (pin "3") (pinfunction "FLGB_3") (pintype "open_collector"))
    )
    (net (code "34") (name "OCS_N3") (class "Default")
      (node (ref "U1") (pin "19") (pinfunction "OCS_N3_19") (pintype "bidirectional"))
      (node (ref "U5") (pin "2") (pinfunction "FLGA_2") (pintype "open_collector"))
    )
    (net (code "35") (name "OCS_N4") (class "Default")
      (node (ref "U1") (pin "21") (pinfunction "OCS_N4_21") (pintype "bidirectional"))
      (node (ref "U5") (pin "3") (pinfunction "FLGB_3") (pintype "open_collector"))
    )
    (net (code "36") (name "PRTPWR1") (class "Default")
      (node (ref "U1") (pin "12") (pinfunction "PRTPWR1/BC_EN1_12") (pintype "bidirectional"))
      (node (ref "U4") (pin "1") (pinfunction "ENA_1") (pintype "input"))
    )
    (net (code "37") (name "PRTPWR2") (class "Default")
      (node (ref "U1") (pin "16") (pinfunction "PRTPWR2/BC_EN2_16") (pintype "bidirectional"))
      (node (ref "U4") (pin "4") (pinfunction "ENB_4") (pintype "input"))
    )
    (net (code "38") (name "PRTPWR3") (class "Default")
      (node (ref "U1") (pin "18") (pinfunction "PRTPWR3/BC_EN3_18") (pintype "bidirectional"))
      (node (ref "U5") (pin "1") (pinfunction "ENA_1") (pintype "input"))
    )
    (net (code "39") (name "PRTPWR4") (class "Default")
      (node (ref "U1") (pin "20") (pinfunction "PRTPWR4/BC_EN4_20") (pintype "bidirectional"))
      (node (ref "U5") (pin "4") (pinfunction "ENB_4") (pintype "input"))
    )
    (net (code "40") (name "PWR_IC_CN1_VBUS") (class "Default")
      (node (ref "BR1") (pin "3") (pinfunction "3_3") (pintype "bidirectional"))
      (node (ref "C23") (pin "+") (pinfunction "1_+") (pintype "passive"))
      (node (ref "C27") (pin "1") (pinfunction "1_1") (pintype "passive"))
      (node (ref "FB3") (pin "2") (pinfunction "2_2") (pintype "passive"))
      (node (ref "U4") (pin "8") (pinfunction "OUTA_8") (pintype "output"))
    )
    (net (code "41") (name "PWR_IC_CN2_VBUS") (class "Default")
      (node (ref "BR2") (pin "3") (pinfunction "3_3") (pintype "bidirectional"))
      (node (ref "C20") (pin "+") (pinfunction "1_+") (pintype "passive"))
      (node (ref "C21") (pin "1") (pinfunction "1_1") (pintype "passive"))
      (node (ref "FB4") (pin "2") (pinfunction "2_2") (pintype "passive"))
      (node (ref "U4") (pin "5") (pinfunction "OUTB_5") (pintype "output"))
    )
    (net (code "42") (name "PWR_IC_CN3_VBUS") (class "Default")
      (node (ref "BR3") (pin "3") (pinfunction "3_3") (pintype "bidirectional"))
      (node (ref "C25") (pin "+") (pinfunction "1_+") (pintype "passive"))
      (node (ref "C26") (pin "1") (pinfunction "1_1") (pintype "passive"))
      (node (ref "FB5") (pin "2") (pinfunction "2_2") (pintype "passive"))
      (node (ref "U5") (pin "8") (pinfunction "OUTA_8") (pintype "output"))
    )
    (net (code "43") (name "PWR_IC_CN4_VBUS") (class "Default")
      (node (ref "BR4") (pin "3") (pinfunction "3_3") (pintype "bidirectional"))
      (node (ref "C29") (pin "+") (pinfunction "1_+") (pintype "passive"))
      (node (ref "C30") (pin "1") (pinfunction "1_1") (pintype "passive"))
      (node (ref "FB6") (pin "2") (pinfunction "2_2") (pintype "passive"))
      (node (ref "U5") (pin "5") (pinfunction "OUTB_5") (pintype "output"))
    )
    (net (code "44") (name "RST_U2U_RST") (class "Default")
      (node (ref "C40") (pin "1") (pinfunction "1_1") (pintype "passive"))
      (node (ref "R32") (pin "2") (pinfunction "2_2") (pintype "passive"))
      (node (ref "U1") (pin "26") (pinfunction "RESET_N_26") (pintype "bidirectional"))
    )
    (net (code "45") (name "USBDN1_U2U_USBCON_N") (class "Default")
      (node (ref "L1") (pin "4") (pinfunction "4_4") (pintype "bidirectional"))
      (node (ref "R5") (pin "1") (pinfunction "1_1") (pintype "passive"))
      (node (ref "U1") (pin "1") (pinfunction "USBDM_DN1/PRT_DIS_M1_1") (pintype "bidirectional"))
    )
    (net (code "46") (name "USBDN1_U2U_USBCON_P") (class "Default")
      (node (ref "L1") (pin "1") (pinfunction "1_1") (pintype "bidirectional"))
      (node (ref "R7") (pin "2") (pinfunction "2_2") (pintype "passive"))
      (node (ref "U1") (pin "2") (pinfunction "USBDP_DN1/PRT_DIS_P1_2") (pintype "bidirectional"))
    )
    (net (code "47") (name "USBDN2_U2U_USBCON_N") (class "Default")
      (node (ref "L2") (pin "4") (pinfunction "4_4") (pintype "bidirectional"))
      (node (ref "R4") (pin "1") (pinfunction "1_1") (pintype "passive"))
      (node (ref "U1") (pin "3") (pinfunction "USBDM_DN2/PRT_DIS_M2_3") (pintype "bidirectional"))
    )
    (net (code "48") (name "USBDN2_U2U_USBCON_P") (class "Default")
      (node (ref "L2") (pin "1") (pinfunction "1_1") (pintype "bidirectional"))
      (node (ref "R14") (pin "2") (pinfunction "2_2") (pintype "passive"))
      (node (ref "U1") (pin "4") (pinfunction "USBDP_DN2/PRT_DIS_P2_4") (pintype "bidirectional"))
    )
    (net (code "49") (name "USBDN3_U2U_USBCON_N") (class "Default")
      (node (ref "L3") (pin "4") (pinfunction "4_4") (pintype "bidirectional"))
      (node (ref "R3") (pin "1") (pinfunction "1_1") (pintype "passive"))
      (node (ref "U1") (pin "6") (pinfunction "USBDM_DN3/PRT_DIS_M3_6") (pintype "bidirectional"))
    )
    (net (code "50") (name "USBDN3_U2U_USBCON_P") (class "Default")
      (node (ref "L3") (pin "1") (pinfunction "1_1") (pintype "bidirectional"))
      (node (ref "R15") (pin "2") (pinfunction "2_2") (pintype "passive"))
      (node (ref "U1") (pin "7") (pinfunction "USBDP_DN3/PRT_DIS_P3_7") (pintype "bidirectional"))
    )
    (net (code "51") (name "USBDN4_U2U_USBCON_N") (class "Default")
      (node (ref "L4") (pin "4") (pinfunction "4_4") (pintype "bidirectional"))
      (node (ref "R2") (pin "1") (pinfunction "1_1") (pintype "passive"))
      (node (ref "U1") (pin "8") (pinfunction "USBDM_DN4/PRT_DIS_M4_8") (pintype "bidirectional"))
    )
    (net (code "52") (name "USBDN4_U2U_USBCON_P") (class "Default")
      (node (ref "L4") (pin "1") (pinfunction "1_1") (pintype "bidirectional"))
      (node (ref "R16") (pin "2") (pinfunction "2_2") (pintype "passive"))
      (node (ref "U1") (pin "9") (pinfunction "USBDP_DN4/PRT_DIS_P4_9") (pintype "bidirectional"))
    )
    (net (code "53") (name "USBUP_USBCON_U2U_N") (class "Default")
      (node (ref "CONN2") (pin "D-") (pinfunction "D-_D-") (pintype "bidirectional"))
      (node (ref "U1") (pin "30") (pinfunction "USBDM_UP_30") (pintype "bidirectional"))
    )
    (net (code "54") (name "USBUP_USBCON_U2U_P") (class "Default")
      (node (ref "CONN2") (pin "D+") (pinfunction "D+_D+") (pintype "bidirectional"))
      (node (ref "U1") (pin "31") (pinfunction "USBDP_UP_31") (pintype "bidirectional"))
    )
    (net (code "55") (name "VBUS_UP") (class "Default")
      (node (ref "C22") (pin "1") (pinfunction "1_1") (pintype "passive"))
      (node (ref "C39") (pin "1") (pinfunction "1_1") (pintype "passive"))
      (node (ref "CONN2") (pin "VBUS") (pinfunction "VBUS_VBUS") (pintype "power_in"))
      (node (ref "D2") (pin "1") (pinfunction "1_1") (pintype "bidirectional"))
      (node (ref "R28") (pin "2") (pinfunction "2_2") (pintype "passive"))
    )
    (net (code "56") (name "VCC") (class "Default")
      (node (ref "C1") (pin "+") (pinfunction "1_+") (pintype "passive"))
      (node (ref "C7") (pin "1") (pinfunction "1_1") (pintype "passive"))
      (node (ref "D1") (pin "P$2") (pinfunction "3_P$2") (pintype "passive"))
      (node (ref "D2") (pin "3") (pinfunction "3_3") (pintype "bidirectional"))
      (node (ref "D3") (pin "1") (pinfunction "1_1") (pintype "bidirectional"))
      (node (ref "D3") (pin "2") (pinfunction "2_2") (pintype "bidirectional"))
      (node (ref "F1") (pin "1") (pinfunction "1_1") (pintype "passive"))
      (node (ref "U3") (pin "3") (pinfunction "ON/OFF_CONTROL_3") (pintype "bidirectional"))
      (node (ref "U3") (pin "4") (pinfunction "DC_INPUT(VIN)_4") (pintype "bidirectional"))
      (node (ref "U4") (pin "7") (pinfunction "IN_7") (pintype "input"))
      (node (ref "U5") (pin "7") (pinfunction "IN_7") (pintype "input"))
    )
  )
)
